# SCH_Mach_DK_Relay_1_Kenh.net
KiCad netlist of a schematic drawn in Altium Designer
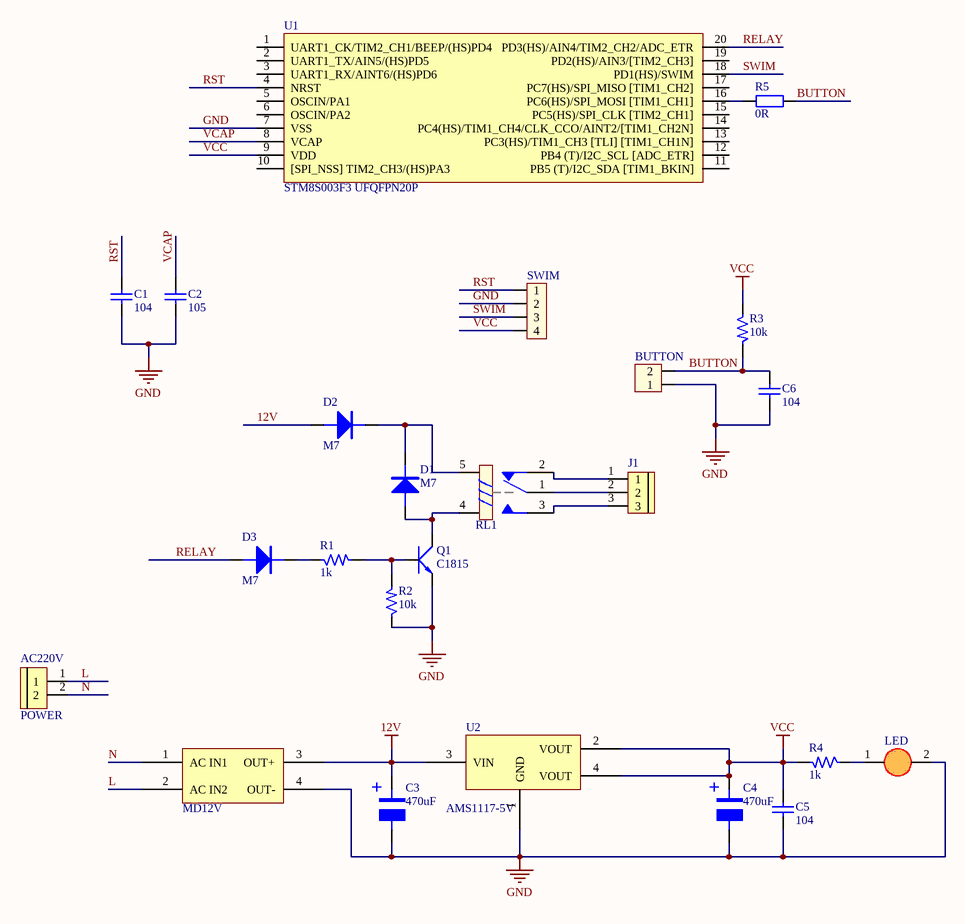
[diagram p0: SCH_Mach_DK_Relay_1_Kenh.SchDoc]

(export (version "E")
  (design (tool "Eeschema 10.0.6"))
  (components
    (comp (ref "AC220V")
      (value "POWER")
      (footprint "BIG_Header 2")
      (description "Big Header 2")
      (libsource (lib "MH_THU VIEN CHUAN 12-03-2015") (part "Header 2"))
    )
    (comp (ref "BUTTON")
      (value "Header 2")
      (footprint "Header 2 Duc Thang 2.54")
      (description "Header 2 (Green)")
      (libsource (lib "MH_THU VIEN CHUAN 12-03-2015") (part "Hed2"))
    )
    (comp (ref "C1")
      (value "104")
      (footprint "Tu 0805")
      (libsource (lib "MH_THU VIEN CHUAN 12-03-2015") (part "CAP 0805"))
    )
    (comp (ref "C2")
      (value "105")
      (footprint "Tu 0805")
      (libsource (lib "MH_THU VIEN CHUAN 12-03-2015") (part "CAP 0805"))
    )
    (comp (ref "C3")
      (value "470uF")
      (footprint "MH_THU VIEN CHUAN 13-03-2015 :Tu Hoa 450uF - 16V")
      (libsource (lib "MH_THU VIEN CHUAN 12-03-2015") (part "Cap100uF 50V"))
    )
    (comp (ref "C4")
      (value "470uF")
      (footprint "MH_THU VIEN CHUAN 13-03-2015 :Tu Hoa 450uF - 16V")
      (libsource (lib "MH_THU VIEN CHUAN 12-03-2015") (part "Cap100uF 50V"))
    )
    (comp (ref "C5")
      (value "104")
      (footprint "Tu 0805")
      (libsource (lib "MH_THU VIEN CHUAN 12-03-2015") (part "CAP 0805"))
    )
    (comp (ref "C6")
      (value "104")
      (footprint "Tu 0805")
      (libsource (lib "MH_THU VIEN CHUAN 12-03-2015") (part "CAP 0805"))
    )
    (comp (ref "D1")
      (value "M7")
      (footprint "SMB")
      (description "Diode")
      (libsource (lib "MH_THU VIEN CHUAN 12-03-2015") (part "DIODE"))
    )
    (comp (ref "D2")
      (value "M7")
      (footprint "SMB")
      (description "Diode")
      (libsource (lib "MH_THU VIEN CHUAN 12-03-2015") (part "DIODE"))
    )
    (comp (ref "D3")
      (value "M7")
      (footprint "SMB")
      (description "Diode")
      (libsource (lib "MH_THU VIEN CHUAN 12-03-2015") (part "DIODE"))
    )
    (comp (ref "J1")
      (value "BIG_Header 3")
      (footprint "BIG_Header 3")
      (libsource (lib "MH_THU VIEN CHUAN 12-03-2015") (part "BIG_Header 3"))
    )
    (comp (ref "LED")
      (value "LED3")
      (footprint "LED RED 5mm")
      (description "LED 3mm")
      (libsource (lib "MH_THU VIEN CHUAN 12-03-2015") (part "LED 3mm"))
    )
    (comp (ref "MD12V")
      (value "Module Driver LED 1x3W")
      (footprint "Module Driver LED")
      (libsource (lib "MH_THU VIEN CHUAN 12-03-2015") (part "Module DK LED 1X3w"))
    )
    (comp (ref "Q1")
      (value "C1815")
      (footprint "SOT23B")
      (description "NPN 600mW, ECB")
      (libsource (lib "MH_THU VIEN CHUAN 12-03-2015") (part "C1815"))
    )
    (comp (ref "R1")
      (value "1k")
      (footprint "Tro SMD 0805")
      (description "Resistor 1/4W")
      (libsource (lib "MH_THU VIEN CHUAN 12-03-2015") (part "Res"))
    )
    (comp (ref "R2")
      (value "10k")
      (footprint "Tro SMD 0805")
      (description "Resistor 1/4W")
      (libsource (lib "MH_THU VIEN CHUAN 12-03-2015") (part "Res"))
    )
    (comp (ref "R3")
      (value "10k")
      (footprint "Tro SMD 0805")
      (description "Resistor 1/4W")
      (libsource (lib "MH_THU VIEN CHUAN 12-03-2015") (part "Res"))
    )
    (comp (ref "R4")
      (value "1k")
      (footprint "Tro SMD 0805")
      (description "Resistor 1/4W")
      (libsource (lib "MH_THU VIEN CHUAN 12-03-2015") (part "Res"))
    )
    (comp (ref "R5")
      (value "0R")
      (footprint "1206 SMD")
      (description "Resistor 1/4W")
      (libsource (lib "MH_THU VIEN CHUAN 12-03-2015") (part "R1/4W"))
    )
    (comp (ref "RL1")
      (value "Relay ?V - 10A")
      (footprint "RELAY5PIN-10A")
      (description "Relay SPDT,10A - 12VDC 5 Pin")
      (libsource (lib "MH_THU VIEN CHUAN 12-03-2015") (part "Relay 10A"))
    )
    (comp (ref "SWIM")
      (value "JP4")
      (footprint "JP4")
      (libsource (lib "MH_THU VIEN CHUAN 12-03-2015") (part "JP4"))
    )
    (comp (ref "U1")
      (value "STM8S003F3 UFQFPN20P")
      (footprint "TSSOP20")
      (libsource (lib "MH_THU VIEN CHUAN 12-03-2015") (part "STM8S003F3 UFQFPN20P"))
    )
    (comp (ref "U2")
      (value "AMS1117-5V")
      (footprint "SOT223-4N")
      (description "AMS")
      (libsource (lib "MH_THU VIEN CHUAN 12-03-2015") (part "AMS1117"))
    )
  )
  (nets
    (net (code "1") (name "/BUTTON") (class "Default")
      (node (ref "BUTTON") (pin "2") (pinfunction "2_2") (pintype "passive"))
      (node (ref "C6") (pin "2") (pinfunction "2_2") (pintype "passive"))
      (node (ref "R3") (pin "2") (pinfunction "2_2") (pintype "passive"))
      (node (ref "R5") (pin "2") (pinfunction "2_2") (pintype "passive"))
    )
    (net (code "2") (name "/L") (class "Default")
      (node (ref "AC220V") (pin "1") (pinfunction "1_1") (pintype "passive"))
      (node (ref "MD12V") (pin "2") (pinfunction "AC_IN2_2") (pintype "passive"))
    )
    (net (code "3") (name "/N") (class "Default")
      (node (ref "AC220V") (pin "2") (pinfunction "2_2") (pintype "passive"))
      (node (ref "MD12V") (pin "1") (pinfunction "AC_IN1_1") (pintype "passive"))
    )
    (net (code "4") (name "/RELAY") (class "Default")
      (node (ref "D3") (pin "1") (pinfunction "1_1") (pintype "passive"))
      (node (ref "U1") (pin "20") (pinfunction "PD3(HS)/AIN4/TIM2_CH2/ADC_ETR_20") (pintype "passive"))
    )
    (net (code "5") (name "/RST") (class "Default")
      (node (ref "C1") (pin "2") (pinfunction "2_2") (pintype "passive"))
      (node (ref "SWIM") (pin "1") (pinfunction "1_1") (pintype "passive"))
      (node (ref "U1") (pin "4") (pinfunction "NRST_4") (pintype "passive"))
    )
    (net (code "6") (name "/SWIM") (class "Default")
      (node (ref "SWIM") (pin "3") (pinfunction "3_3") (pintype "passive"))
      (node (ref "U1") (pin "18") (pinfunction "PD1(HS)/SWIM_18") (pintype "passive"))
    )
    (net (code "7") (name "/VCAP") (class "Default")
      (node (ref "C2") (pin "2") (pinfunction "2_2") (pintype "passive"))
      (node (ref "U1") (pin "8") (pinfunction "VCAP_8") (pintype "passive"))
    )
    (net (code "8") (name "12V") (class "Default")
      (node (ref "C3") (pin "1") (pinfunction "1_1") (pintype "passive"))
      (node (ref "D2") (pin "1") (pinfunction "1_1") (pintype "passive"))
      (node (ref "MD12V") (pin "3") (pinfunction "OUT+_3") (pintype "passive"))
      (node (ref "U2") (pin "3") (pinfunction "VIN_3") (pintype "passive"))
    )
    (net (code "9") (name "GND") (class "Default")
      (node (ref "BUTTON") (pin "1") (pinfunction "1_1") (pintype "passive"))
      (node (ref "C1") (pin "1") (pinfunction "1_1") (pintype "passive"))
      (node (ref "C2") (pin "1") (pinfunction "1_1") (pintype "passive"))
      (node (ref "C3") (pin "2") (pinfunction "2_2") (pintype "passive"))
      (node (ref "C4") (pin "2") (pinfunction "2_2") (pintype "passive"))
      (node (ref "C5") (pin "1") (pinfunction "1_1") (pintype "passive"))
      (node (ref "C6") (pin "1") (pinfunction "1_1") (pintype "passive"))
      (node (ref "LED") (pin "2") (pinfunction "K_2") (pintype "passive"))
      (node (ref "MD12V") (pin "4") (pinfunction "OUT-_4") (pintype "passive"))
      (node (ref "Q1") (pin "3") (pinfunction "E_3") (pintype "passive"))
      (node (ref "R2") (pin "1") (pinfunction "1_1") (pintype "passive"))
      (node (ref "SWIM") (pin "2") (pinfunction "2_2") (pintype "passive"))
      (node (ref "U1") (pin "7") (pinfunction "VSS_7") (pintype "passive"))
      (node (ref "U2") (pin "1") (pinfunction "GND_1") (pintype "passive"))
    )
    (net (code "10") (name "Net-(D1-Pad2)") (class "Default")
      (node (ref "D1") (pin "2") (pinfunction "2_2") (pintype "passive"))
      (node (ref "D2") (pin "2") (pinfunction "2_2") (pintype "passive"))
      (node (ref "RL1") (pin "5") (pinfunction "5_5") (pintype "passive"))
    )
    (net (code "11") (name "Net-(D3-Pad2)") (class "Default")
      (node (ref "D3") (pin "2") (pinfunction "2_2") (pintype "passive"))
      (node (ref "R1") (pin "1") (pinfunction "1_1") (pintype "passive"))
    )
    (net (code "12") (name "Net-(J1-Pad1)") (class "Default")
      (node (ref "J1") (pin "1") (pinfunction "1_1") (pintype "passive"))
      (node (ref "RL1") (pin "2") (pinfunction "2_2") (pintype "passive"))
    )
    (net (code "13") (name "Net-(J1-Pad2)") (class "Default")
      (node (ref "J1") (pin "2") (pinfunction "2_2") (pintype "passive"))
      (node (ref "RL1") (pin "1") (pinfunction "1_1") (pintype "passive"))
    )
    (net (code "14") (name "Net-(J1-Pad3)") (class "Default")
      (node (ref "J1") (pin "3") (pinfunction "3_3") (pintype "passive"))
      (node (ref "RL1") (pin "3") (pinfunction "3_3") (pintype "passive"))
    )
    (net (code "15") (name "Net-(LED-A)") (class "Default")
      (node (ref "LED") (pin "1") (pinfunction "A_1") (pintype "passive"))
      (node (ref "R4") (pin "1") (pinfunction "1_1") (pintype "passive"))
    )
    (net (code "16") (name "Net-(Q1-B)") (class "Default")
      (node (ref "Q1") (pin "1") (pinfunction "B_1") (pintype "passive"))
      (node (ref "R1") (pin "2") (pinfunction "2_2") (pintype "passive"))
      (node (ref "R2") (pin "2") (pinfunction "2_2") (pintype "passive"))
    )
    (net (code "17") (name "Net-(Q1-C)") (class "Default")
      (node (ref "D1") (pin "1") (pinfunction "1_1") (pintype "passive"))
      (node (ref "Q1") (pin "2") (pinfunction "C_2") (pintype "passive"))
      (node (ref "RL1") (pin "4") (pinfunction "4_4") (pintype "passive"))
    )
    (net (code "18") (name "Net-(U1-PC6(HS){slash}SPI_MOSI_[TIM1_CH1])") (class "Default")
      (node (ref "R5") (pin "1") (pinfunction "1_1") (pintype "passive"))
      (node (ref "U1") (pin "16") (pinfunction "PC6(HS)/SPI_MOSI_[TIM1_CH1]_16") (pintype "passive"))
    )
    (net (code "19") (name "VCC") (class "Default")
      (node (ref "C4") (pin "1") (pinfunction "1_1") (pintype "passive"))
      (node (ref "C5") (pin "2") (pinfunction "2_2") (pintype "passive"))
      (node (ref "R3") (pin "1") (pinfunction "1_1") (pintype "passive"))
      (node (ref "R4") (pin "2") (pinfunction "2_2") (pintype "passive"))
      (node (ref "SWIM") (pin "4") (pinfunction "4_4") (pintype "passive"))
      (node (ref "U1") (pin "9") (pinfunction "VDD_9") (pintype "passive"))
      (node (ref "U2") (pin "2") (pinfunction "VOUT_2") (pintype "passive"))
      (node (ref "U2") (pin "4") (pinfunction "VOUT_4") (pintype "passive"))
    )
    (net (code "20") (name "unconnected-(U1-OSCIN{slash}PA1-Pad5)") (class "Default")
      (node (ref "U1") (pin "5") (pinfunction "OSCIN/PA1_5") (pintype "passive"))
    )
    (net (code "21") (name "unconnected-(U1-OSCIN{slash}PA2-Pad6)") (class "Default")
      (node (ref "U1") (pin "6") (pinfunction "OSCIN/PA2_6") (pintype "passive"))
    )
    (net (code "22") (name "unconnected-(U1-PB4_(T){slash}I2C_SCL_[ADC_ETR]-Pad12)") (class "Default")
      (node (ref "U1") (pin "12") (pinfunction "PB4_(T)/I2C_SCL_[ADC_ETR]_12") (pintype "passive"))
    )
    (net (code "23") (name "unconnected-(U1-PB5_(T){slash}I2C_SDA_[TIM1_BKIN]-Pad11)") (class "Default")
      (node (ref "U1") (pin "11") (pinfunction "PB5_(T)/I2C_SDA_[TIM1_BKIN]_11") (pintype "passive"))
    )
    (net (code "24") (name "unconnected-(U1-PC3(HS){slash}TIM1_CH3_[TLI]_[TIM1_CH1N]-Pad13)") (class "Default")
      (node (ref "U1") (pin "13") (pinfunction "PC3(HS)/TIM1_CH3_[TLI]_[TIM1_CH1N]_13") (pintype "passive"))
    )
    (net (code "25") (name "unconnected-(U1-PC4(HS){slash}TIM1_CH4{slash}CLK_CCO{slash}AINT2{slash}[TIM1_CH2N]-Pad14)") (class "Default")
      (node (ref "U1") (pin "14") (pinfunction "PC4(HS)/TIM1_CH4/CLK_CCO/AINT2/[TIM1_CH2N]_14") (pintype "passive"))
    )
    (net (code "26") (name "unconnected-(U1-PC5(HS){slash}SPI_CLK_[TIM2_CH1]-Pad15)") (class "Default")
      (node (ref "U1") (pin "15") (pinfunction "PC5(HS)/SPI_CLK_[TIM2_CH1]_15") (pintype "passive"))
    )
    (net (code "27") (name "unconnected-(U1-PC7(HS){slash}SPI_MISO_[TIM1_CH2]-Pad17)") (class "Default")
      (node (ref "U1") (pin "17") (pinfunction "PC7(HS)/SPI_MISO_[TIM1_CH2]_17") (pintype "passive"))
    )
    (net (code "28") (name "unconnected-(U1-PD2(HS){slash}AIN3{slash}[TIM2_CH3]-Pad19)") (class "Default")
      (node (ref "U1") (pin "19") (pinfunction "PD2(HS)/AIN3/[TIM2_CH3]_19") (pintype "passive"))
    )
    (net (code "29") (name "unconnected-(U1-UART1_CK{slash}TIM2_CH1{slash}BEEP{slash}(HS)PD4-Pad1)") (class "Default")
      (node (ref "U1") (pin "1") (pinfunction "UART1_CK/TIM2_CH1/BEEP/(HS)PD4_1") (pintype "passive"))
    )
    (net (code "30") (name "unconnected-(U1-UART1_RX{slash}AINT6{slash}(HS)PD6-Pad3)") (class "Default")
      (node (ref "U1") (pin "3") (pinfunction "UART1_RX/AINT6/(HS)PD6_3") (pintype "passive"))
    )
    (net (code "31") (name "unconnected-(U1-UART1_TX{slash}AIN5{slash}(HS)PD5-Pad2)") (class "Default")
      (node (ref "U1") (pin "2") (pinfunction "UART1_TX/AIN5/(HS)PD5_2") (pintype "passive"))
    )
    (net (code "32") (name "unconnected-(U1-[SPI_NSS]_TIM2_CH3{slash}(HS)PA3-Pad10)") (class "Default")
      (node (ref "U1") (pin "10") (pinfunction "[SPI_NSS]_TIM2_CH3/(HS)PA3_10") (pintype "passive"))
    )
  )
)
